# Linear_Slider.net
KiCad netlist of a schematic drawn in EAGLE
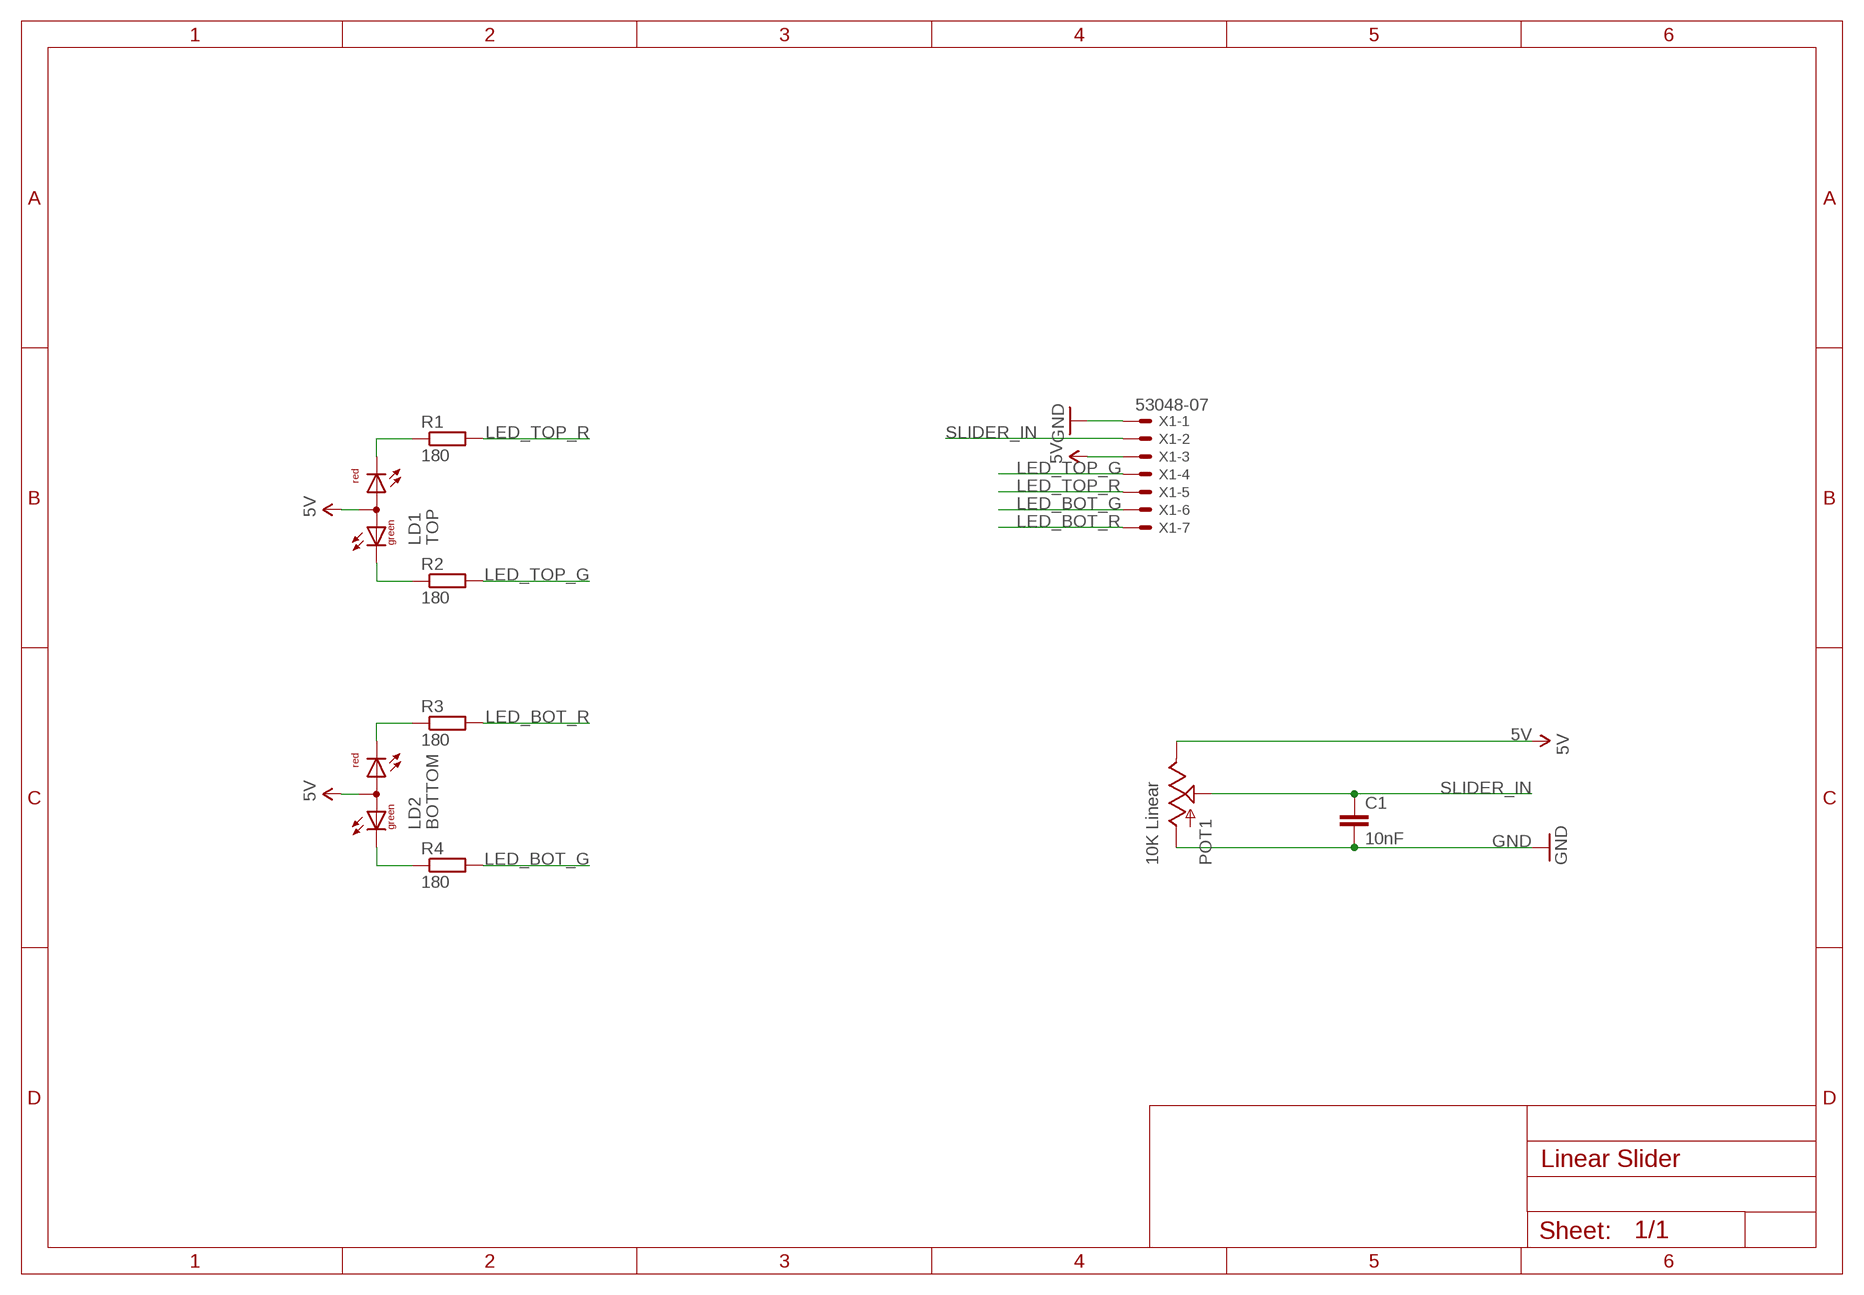
[diagram p0: schematic, sheet 1]

(export (version "E")
  (design (tool "Eeschema 10.0.6"))
  (components
    (comp (ref "C1")
      (value "10nF")
      (footprint "eagle-import:0603-CAP")
      (libsource (lib "eagle-import") (part "CAP0603-CAP"))
    )
    (comp (ref "LD1")
      (value "TOP")
      (footprint "eagle-import:DUOLED-A-5MM")
      (libsource (lib "eagle-import") (part "DUOLED-RG-A"))
    )
    (comp (ref "LD2")
      (value "BOTTOM")
      (footprint "eagle-import:DUOLED-A-5MM")
      (libsource (lib "eagle-import") (part "DUOLED-RG-A"))
    )
    (comp (ref "POT1")
      (value "10K Linear")
      (footprint "eagle-import:SLIDER60")
      (libsource (lib "eagle-import") (part "SLIDER60"))
    )
    (comp (ref "R1")
      (value "180")
      (footprint "eagle-import:R0603")
      (libsource (lib "eagle-import") (part "R-EU_R0603"))
    )
    (comp (ref "R2")
      (value "180")
      (footprint "eagle-import:R0603")
      (libsource (lib "eagle-import") (part "R-EU_R0603"))
    )
    (comp (ref "R3")
      (value "180")
      (footprint "eagle-import:R0603")
      (libsource (lib "eagle-import") (part "R-EU_R0603"))
    )
    (comp (ref "R4")
      (value "180")
      (footprint "eagle-import:R0603")
      (libsource (lib "eagle-import") (part "R-EU_R0603"))
    )
    (comp (ref "X1")
      (value "53048-07")
      (footprint "eagle-import:53048-07")
      (fields (field (name "MPN") "53048-0710"))
      (libsource (lib "eagle-import") (part "53?-07048"))
    )
  )
  (nets
    (net (code "1") (name "/LED_BOT_G") (class "Default")
      (node (ref "R4") (pin "2") (pinfunction "2_2") (pintype "passive"))
      (node (ref "X1") (pin "6") (pinfunction "S_6") (pintype "passive"))
    )
    (net (code "2") (name "/LED_BOT_R") (class "Default")
      (node (ref "R3") (pin "2") (pinfunction "2_2") (pintype "passive"))
      (node (ref "X1") (pin "7") (pinfunction "S_7") (pintype "passive"))
    )
    (net (code "3") (name "/LED_TOP_G") (class "Default")
      (node (ref "R2") (pin "2") (pinfunction "2_2") (pintype "passive"))
      (node (ref "X1") (pin "4") (pinfunction "S_4") (pintype "passive"))
    )
    (net (code "4") (name "/LED_TOP_R") (class "Default")
      (node (ref "R1") (pin "2") (pinfunction "2_2") (pintype "passive"))
      (node (ref "X1") (pin "5") (pinfunction "S_5") (pintype "passive"))
    )
    (net (code "5") (name "/SLIDER_IN") (class "Default")
      (node (ref "C1") (pin "1") (pinfunction "1_1") (pintype "passive"))
      (node (ref "POT1") (pin "2A") (pinfunction "S_2A") (pintype "passive"))
      (node (ref "X1") (pin "2") (pinfunction "S_2") (pintype "passive"))
    )
    (net (code "6") (name "5V") (class "Default")
      (node (ref "LD1") (pin "A") (pinfunction "A_A") (pintype "passive"))
      (node (ref "LD2") (pin "A") (pinfunction "A_A") (pintype "passive"))
      (node (ref "POT1") (pin "1") (pinfunction "E_1") (pintype "passive"))
      (node (ref "X1") (pin "3") (pinfunction "S_3") (pintype "passive"))
    )
    (net (code "7") (name "GND") (class "Default")
      (node (ref "C1") (pin "2") (pinfunction "2_2") (pintype "passive"))
      (node (ref "POT1") (pin "3") (pinfunction "A_3") (pintype "passive"))
      (node (ref "X1") (pin "1") (pinfunction "S_1") (pintype "passive"))
    )
    (net (code "8") (name "Net-(LD1-CG)") (class "Default")
      (node (ref "LD1") (pin "CX") (pinfunction "CG_CX") (pintype "passive"))
      (node (ref "R2") (pin "1") (pinfunction "1_1") (pintype "passive"))
    )
    (net (code "9") (name "Net-(LD1-PadCR)") (class "Default")
      (node (ref "LD1") (pin "CR") (pinfunction "CR_CR") (pintype "passive"))
      (node (ref "R1") (pin "1") (pinfunction "1_1") (pintype "passive"))
    )
    (net (code "10") (name "Net-(LD2-CG)") (class "Default")
      (node (ref "LD2") (pin "CX") (pinfunction "CG_CX") (pintype "passive"))
      (node (ref "R4") (pin "1") (pinfunction "1_1") (pintype "passive"))
    )
    (net (code "11") (name "Net-(LD2-PadCR)") (class "Default")
      (node (ref "LD2") (pin "CR") (pinfunction "CR_CR") (pintype "passive"))
      (node (ref "R3") (pin "1") (pinfunction "1_1") (pintype "passive"))
    )
  )
)
